# pca63100_top.net
KiCad netlist of a schematic drawn in Altium Designer
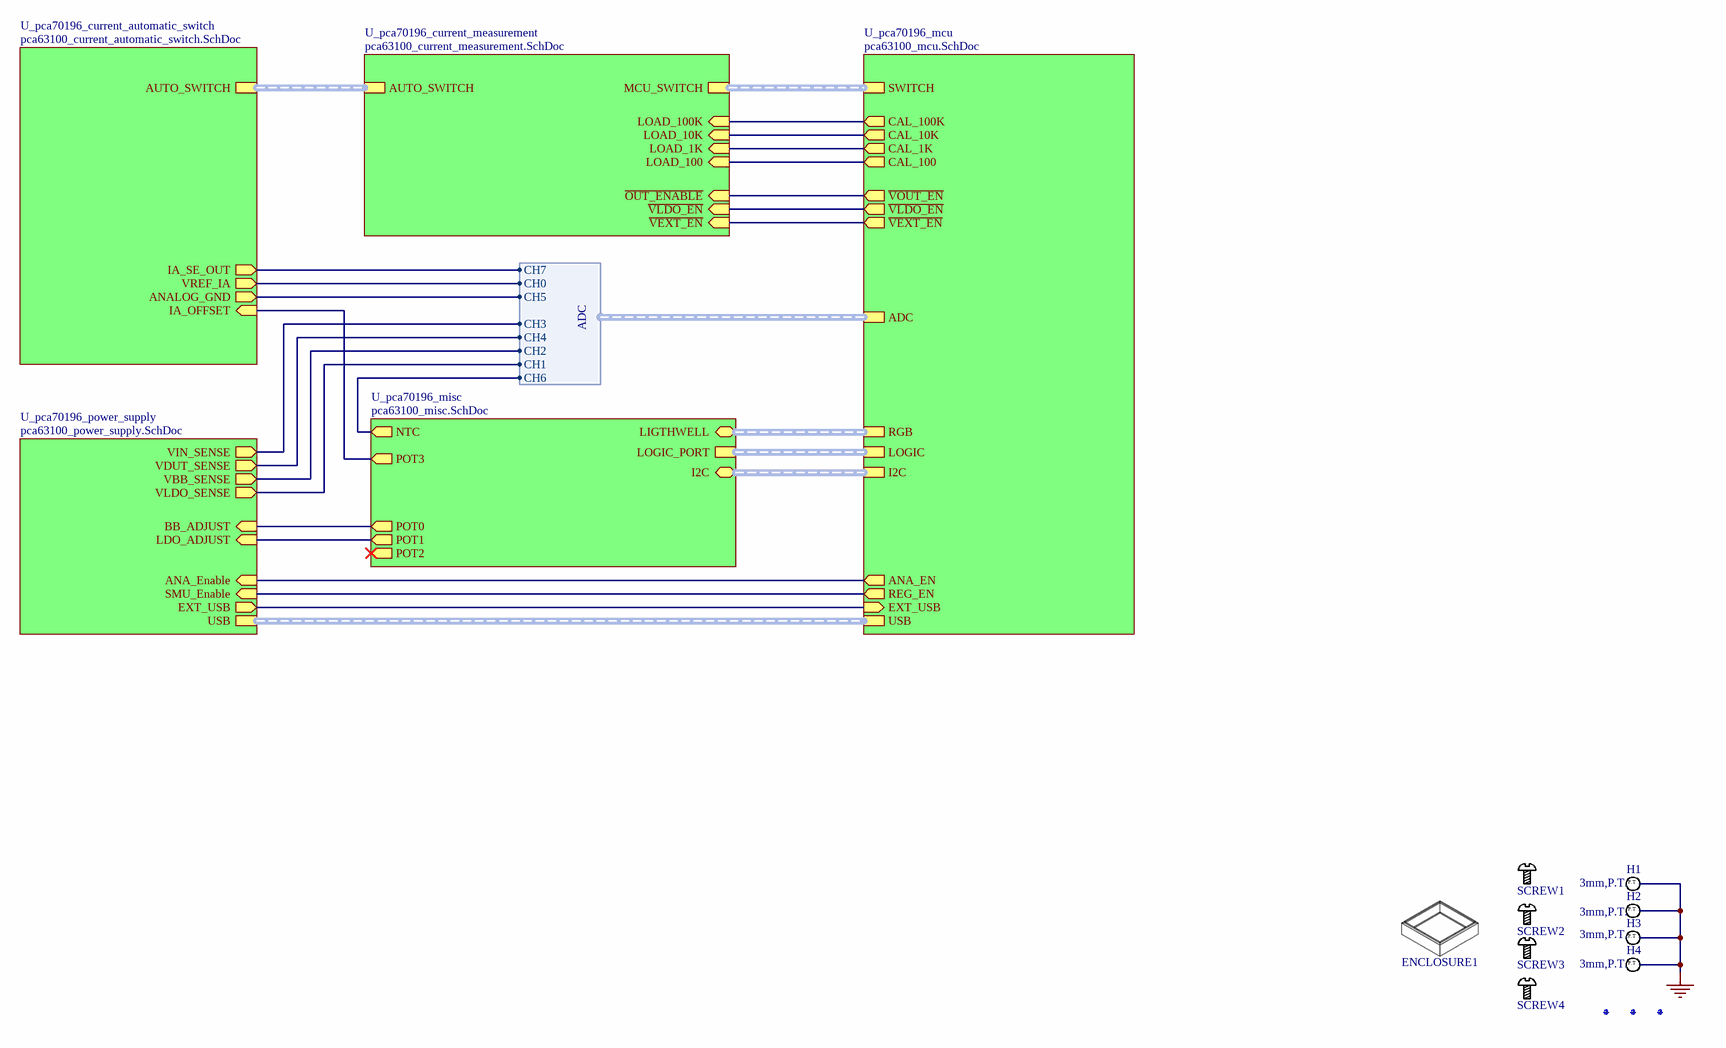
[diagram p0: pca63100_top.SchDoc]

(export (version "E")
  (design (tool "Eeschema 10.0.6"))
  (components
    (comp (ref "ENCLOSURE1")
      (value "Plastic Enclosure")
      (footprint "Enclosure_PPK2")
      (description "PPK2 Moulded plastic casing")
      (fields
        (field (name "PART NUMBER") "Enclosure_PPK2")
        (field (name "MANUFACTURER") "Proto Labs, Inc.")
        (field (name "PUBLISHER") "Nordic Semiconductor")
      )
      (libsource (lib "AltiumLib") (part "Enclosure"))
    )
    (comp (ref "Fid1")
      (value "Fiducial mark")
      (footprint "Fiducial_Round-Square")
      (description "Fiducial Mark")
      (fields
        (field (name "PART NUMBER") "Fid-Mark-Round-Square")
        (field (name "PUBLISHER") "Nordic Semiconductor")
      )
      (libsource (lib "AltiumLib") (part "Fiducial"))
    )
    (comp (ref "Fid2")
      (value "Fiducial mark")
      (footprint "Fiducial_Round-Square")
      (description "Fiducial Mark")
      (fields
        (field (name "PART NUMBER") "Fid-Mark-Round-Square")
        (field (name "PUBLISHER") "Nordic Semiconductor")
      )
      (libsource (lib "AltiumLib") (part "Fiducial"))
    )
    (comp (ref "Fid3")
      (value "Fiducial mark")
      (footprint "Fiducial_Round-Square")
      (description "Fiducial Mark")
      (fields
        (field (name "PART NUMBER") "Fid-Mark-Round-Square")
        (field (name "PUBLISHER") "Nordic Semiconductor")
      )
      (libsource (lib "AltiumLib") (part "Fiducial"))
    )
    (comp (ref "H1")
      (value "3mm,P.T.")
      (footprint "HOLE_PT_3MM")
      (description "Regular Plate Through, 3mm hole")
      (fields
        (field (name "PART NUMBER") "Hole_3MM_PT")
        (field (name "MANUFACTURER") "Nordic Semiconductor")
        (field (name "PUBLISHER") "Nordic Semiconductor")
      )
      (libsource (lib "AltiumLib") (part "HOLE_PT"))
    )
    (comp (ref "H2")
      (value "3mm,P.T.")
      (footprint "HOLE_PT_3MM")
      (description "Regular Plate Through, 3mm hole")
      (fields
        (field (name "PART NUMBER") "Hole_3MM_PT")
        (field (name "MANUFACTURER") "Nordic Semiconductor")
        (field (name "PUBLISHER") "Nordic Semiconductor")
      )
      (libsource (lib "AltiumLib") (part "HOLE_PT"))
    )
    (comp (ref "H3")
      (value "3mm,P.T.")
      (footprint "HOLE_PT_3MM")
      (description "Regular Plate Through, 3mm hole")
      (fields
        (field (name "PART NUMBER") "Hole_3MM_PT")
        (field (name "MANUFACTURER") "Nordic Semiconductor")
        (field (name "PUBLISHER") "Nordic Semiconductor")
      )
      (libsource (lib "AltiumLib") (part "HOLE_PT"))
    )
    (comp (ref "H4")
      (value "3mm,P.T.")
      (footprint "HOLE_PT_3MM")
      (description "Regular Plate Through, 3mm hole")
      (fields
        (field (name "PART NUMBER") "Hole_3MM_PT")
        (field (name "MANUFACTURER") "Nordic Semiconductor")
        (field (name "PUBLISHER") "Nordic Semiconductor")
      )
      (libsource (lib "AltiumLib") (part "HOLE_PT"))
    )
    (comp (ref "SCREW1")
      (value "Screw")
      (footprint "Screw_25x50_pan_tx")
      (description "Pan head, torx, 2.5x5mm screw")
      (fields
        (field (name "PART NUMBER") "Screw_25x50_pan_tx")
        (field (name "MANUFACTURER") "Bossard")
        (field (name "PUBLISHER") "Nordic Semiconductor")
      )
      (libsource (lib "AltiumLib") (part "Screw"))
    )
    (comp (ref "SCREW2")
      (value "Screw")
      (footprint "Screw_25x50_pan_tx")
      (description "Pan head, torx, 2.5x5mm screw")
      (fields
        (field (name "PART NUMBER") "Screw_25x50_pan_tx")
        (field (name "MANUFACTURER") "Bossard")
        (field (name "PUBLISHER") "Nordic Semiconductor")
      )
      (libsource (lib "AltiumLib") (part "Screw"))
    )
    (comp (ref "SCREW3")
      (value "Screw")
      (footprint "Screw_25x50_pan_tx")
      (description "Pan head, torx, 2.5x5mm screw")
      (fields
        (field (name "PART NUMBER") "Screw_25x50_pan_tx")
        (field (name "MANUFACTURER") "Bossard")
        (field (name "PUBLISHER") "Nordic Semiconductor")
      )
      (libsource (lib "AltiumLib") (part "Screw"))
    )
    (comp (ref "SCREW4")
      (value "Screw")
      (footprint "Screw_25x50_pan_tx")
      (description "Pan head, torx, 2.5x5mm screw")
      (fields
        (field (name "PART NUMBER") "Screw_25x50_pan_tx")
        (field (name "MANUFACTURER") "Bossard")
        (field (name "PUBLISHER") "Nordic Semiconductor")
      )
      (libsource (lib "AltiumLib") (part "Screw"))
    )
  )
  (nets
    (net (code "31") (name "GND") (class "Default")
      (node (ref "H1") (pin "1") (pinfunction "1_1") (pintype "passive"))
      (node (ref "H2") (pin "1") (pinfunction "1_1") (pintype "passive"))
      (node (ref "H3") (pin "1") (pinfunction "1_1") (pintype "passive"))
      (node (ref "H4") (pin "1") (pinfunction "1_1") (pintype "passive"))
    )
  )
)
